# TRANSLATOR_4CH.net
KiCad netlist of a schematic drawn in Altium Designer
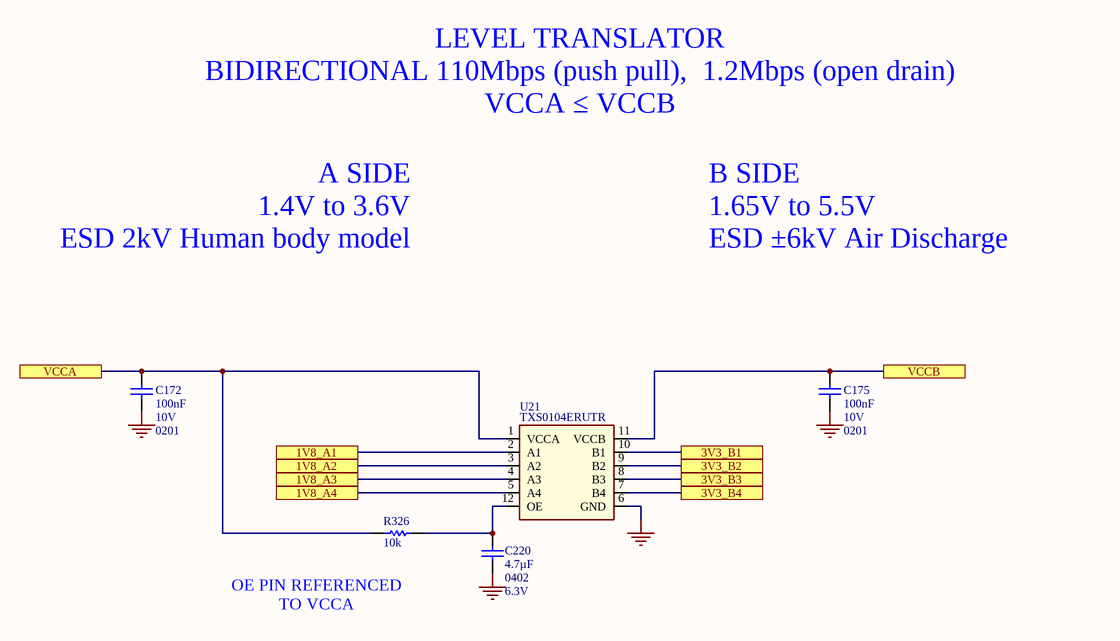
[diagram p0: TRANSLATOR_4CH.SchDoc]

(export (version "E")
  (design (tool "Eeschema 10.0.6"))
  (components
    (comp (ref "C172")
      (value "100nF")
      (footprint "CAP-0201")
      (description "CAP CHIP 0201 100nF 10% 10V X5R")
      (fields
        (field (name "PART NUMBER") "CL03A104KP3NNNC")
        (field (name "MANUFACTURER") "Samsung Electro-Mechanics")
        (field (name "VOLTAGE") "10V")
        (field (name "CASE CODE (IMPERIAL)") "0201")
      )
      (libsource (lib "Clean") (part "CAP"))
    )
    (comp (ref "C175")
      (value "100nF")
      (footprint "CAP-0201")
      (description "CAP CHIP 0201 100nF 10% 10V X5R")
      (fields
        (field (name "PART NUMBER") "CL03A104KP3NNNC")
        (field (name "MANUFACTURER") "Samsung Electro-Mechanics")
        (field (name "VOLTAGE") "10V")
        (field (name "CASE CODE (IMPERIAL)") "0201")
      )
      (libsource (lib "Clean") (part "CAP"))
    )
    (comp (ref "C220")
      (value "4.7µF")
      (footprint "CAP-0402")
      (description "CAP CHIP 0402 4.7uF 20% 6V3 X5R")
      (fields
        (field (name "MANUFACTURER") "Hottech")
        (field (name "PART NUMBER") "C1005A475M6R3NT")
        (field (name "CASE CODE (IMPERIAL)") "0402")
        (field (name "VOLTAGE") "6.3V")
      )
      (libsource (lib "Clean") (part "CAP"))
    )
    (comp (ref "R326")
      (value "10k")
      (footprint "RES-0201")
      (description "RES CHIP 0201 10k 1% 1/20W")
      (fields (field (name "POWER") "50mW") (field (name "TOLERANCE") "1%"))
      (libsource (lib "Clean") (part "RES"))
    )
    (comp (ref "U21")
      (value "TXS0104ERUTR")
      (footprint "TI RUT RUT0012A UQFN 2x1.7x0.55mm 12 pins 0.4mm pitch")
      (fields (field (name "MANUFACTURER") "Texas Instruments"))
      (libsource (lib "Clean") (part "TXS0104ERUTR"))
    )
  )
  (nets
    (net (code "1") (name "/1V8_A1") (class "Default")
      (node (ref "U21") (pin "2") (pinfunction "A1_2") (pintype "power_in"))
    )
    (net (code "2") (name "/1V8_A2") (class "Default")
      (node (ref "U21") (pin "3") (pinfunction "A2_3") (pintype "passive"))
    )
    (net (code "3") (name "/1V8_A3") (class "Default")
      (node (ref "U21") (pin "4") (pinfunction "A3_4") (pintype "power_in"))
    )
    (net (code "4") (name "/1V8_A4") (class "Default")
      (node (ref "U21") (pin "5") (pinfunction "A4_5") (pintype "passive"))
    )
    (net (code "5") (name "/3V3_B1") (class "Default")
      (node (ref "U21") (pin "10") (pinfunction "B1_10") (pintype "passive"))
    )
    (net (code "6") (name "/3V3_B2") (class "Default")
      (node (ref "U21") (pin "9") (pinfunction "B2_9") (pintype "passive"))
    )
    (net (code "7") (name "/3V3_B3") (class "Default")
      (node (ref "U21") (pin "8") (pinfunction "B3_8") (pintype "passive"))
    )
    (net (code "8") (name "/3V3_B4") (class "Default")
      (node (ref "U21") (pin "7") (pinfunction "B4_7") (pintype "passive"))
    )
    (net (code "9") (name "/VCCA") (class "Default")
      (node (ref "C172") (pin "2") (pinfunction "2_2") (pintype "passive"))
      (node (ref "R326") (pin "2") (pinfunction "2_2") (pintype "passive"))
      (node (ref "U21") (pin "1") (pinfunction "VCCA_1") (pintype "passive"))
    )
    (net (code "10") (name "/VCCB") (class "Default")
      (node (ref "C175") (pin "2") (pinfunction "2_2") (pintype "passive"))
      (node (ref "U21") (pin "11") (pinfunction "VCCB_11") (pintype "passive"))
    )
    (net (code "11") (name "GND") (class "Default")
      (node (ref "C172") (pin "1") (pinfunction "1_1") (pintype "passive"))
      (node (ref "C175") (pin "1") (pinfunction "1_1") (pintype "passive"))
      (node (ref "C220") (pin "2") (pinfunction "2_2") (pintype "passive"))
      (node (ref "U21") (pin "6") (pinfunction "GND_6") (pintype "passive"))
    )
    (net (code "12") (name "Net-(U21-OE)") (class "Default")
      (node (ref "C220") (pin "1") (pinfunction "1_1") (pintype "passive"))
      (node (ref "R326") (pin "1") (pinfunction "1_1") (pintype "passive"))
      (node (ref "U21") (pin "12") (pinfunction "OE_12") (pintype "passive"))
    )
  )
)
